# 3_Communication.net
KiCad netlist of a schematic drawn in Altium Designer
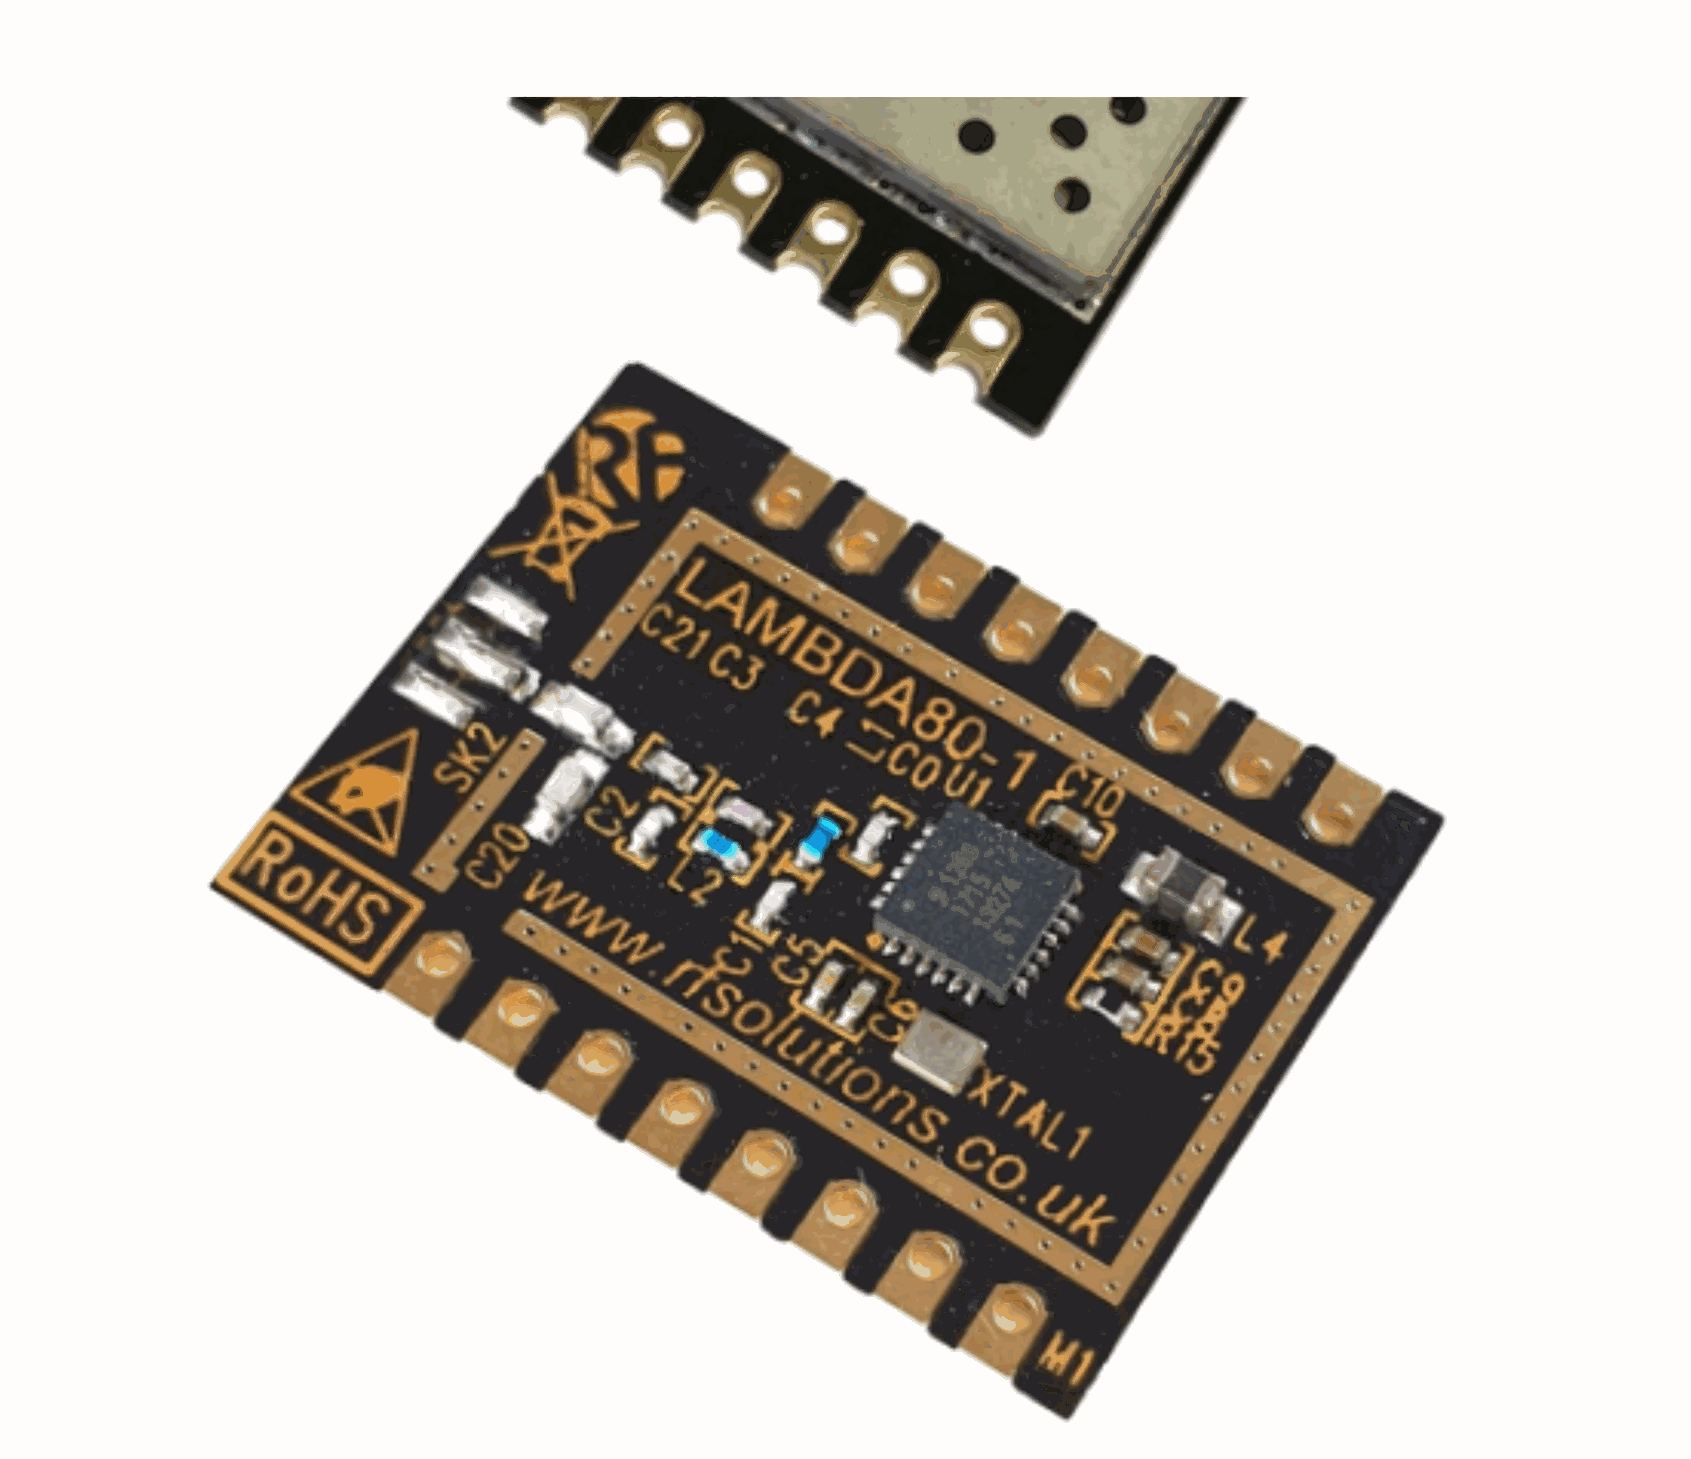
[diagram p0: 3_Communication.SchDoc, top middle]
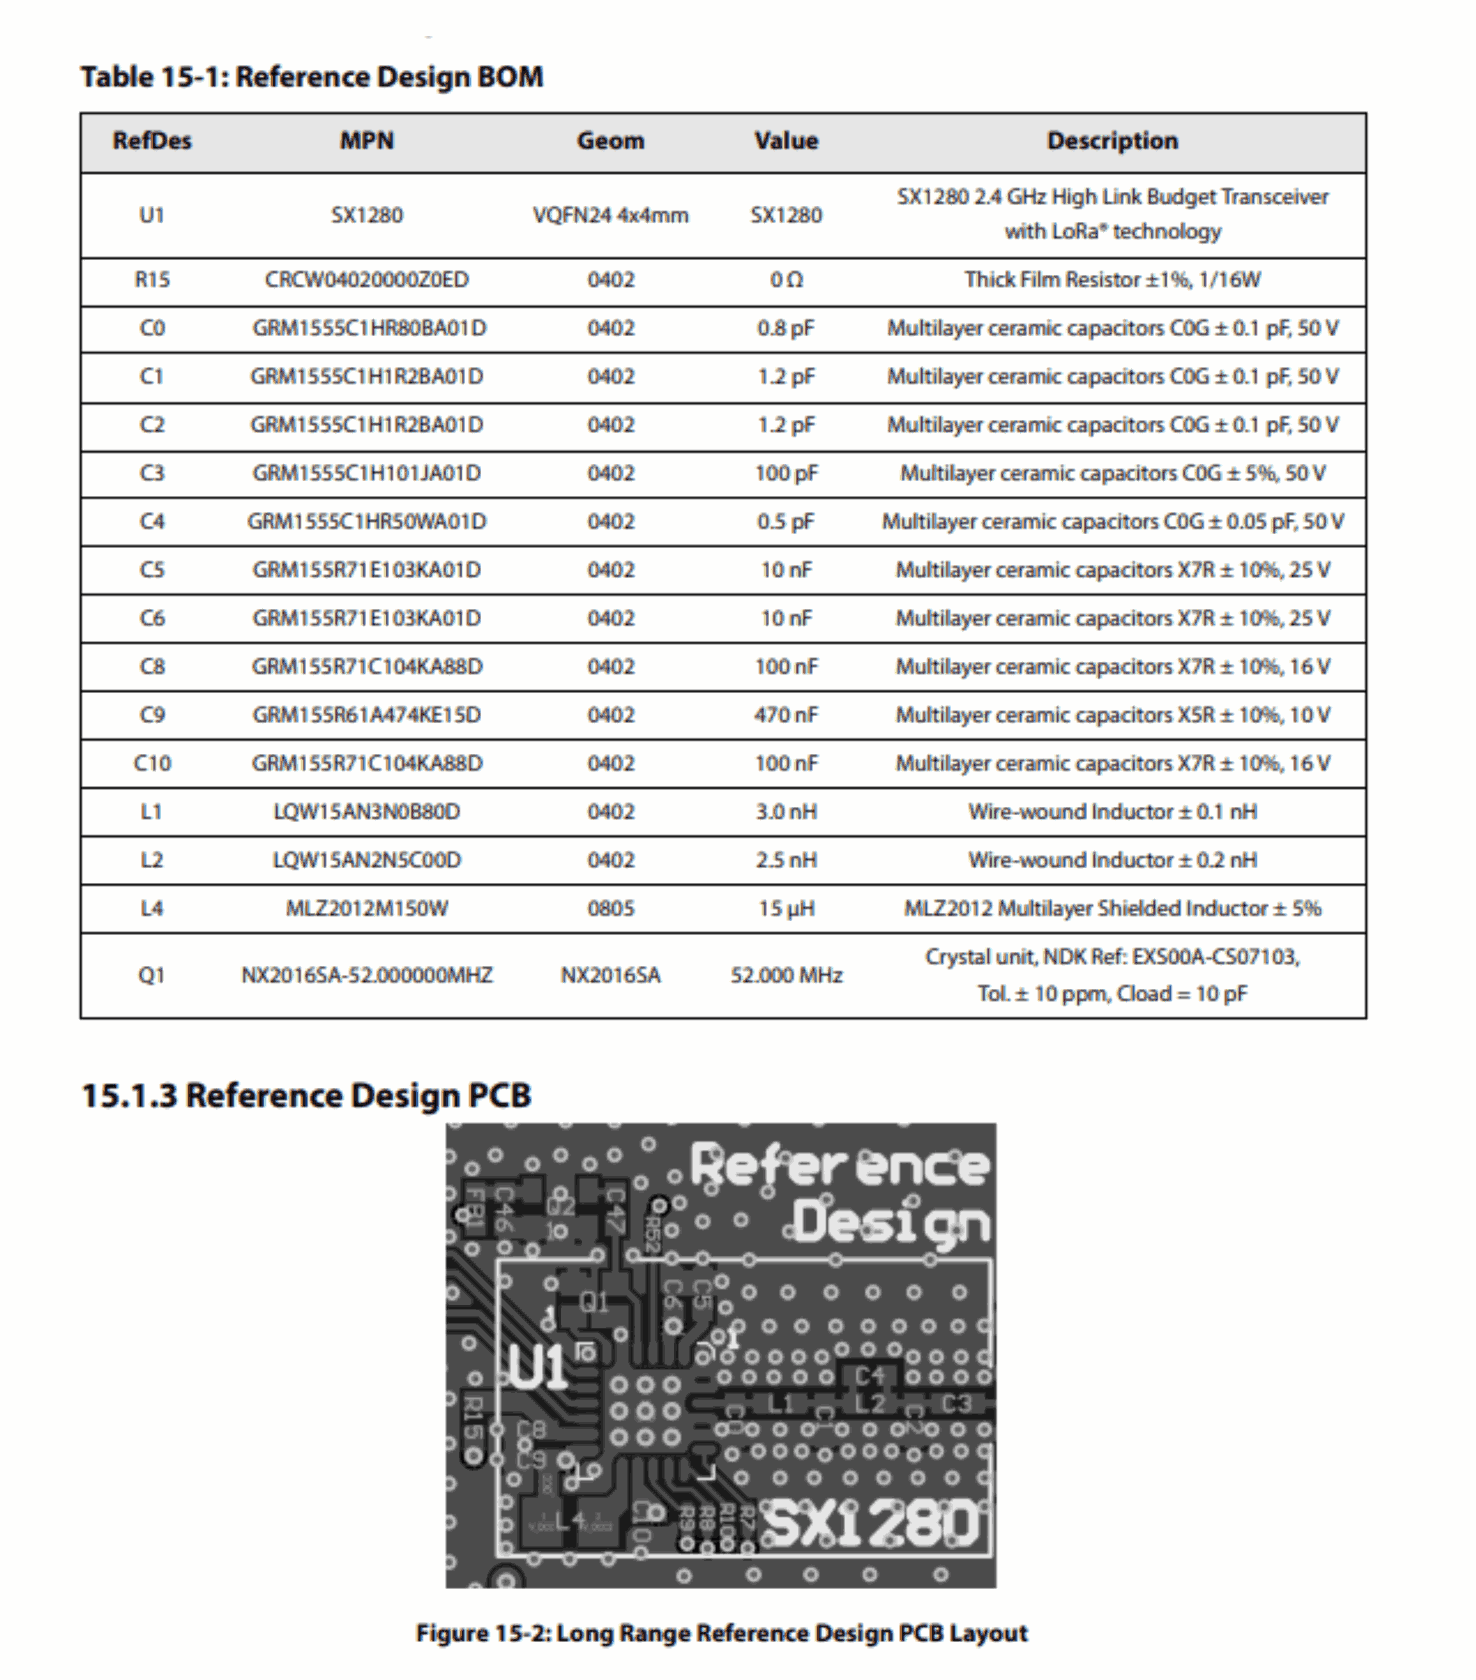
[diagram p1: 3_Communication.SchDoc, top right]
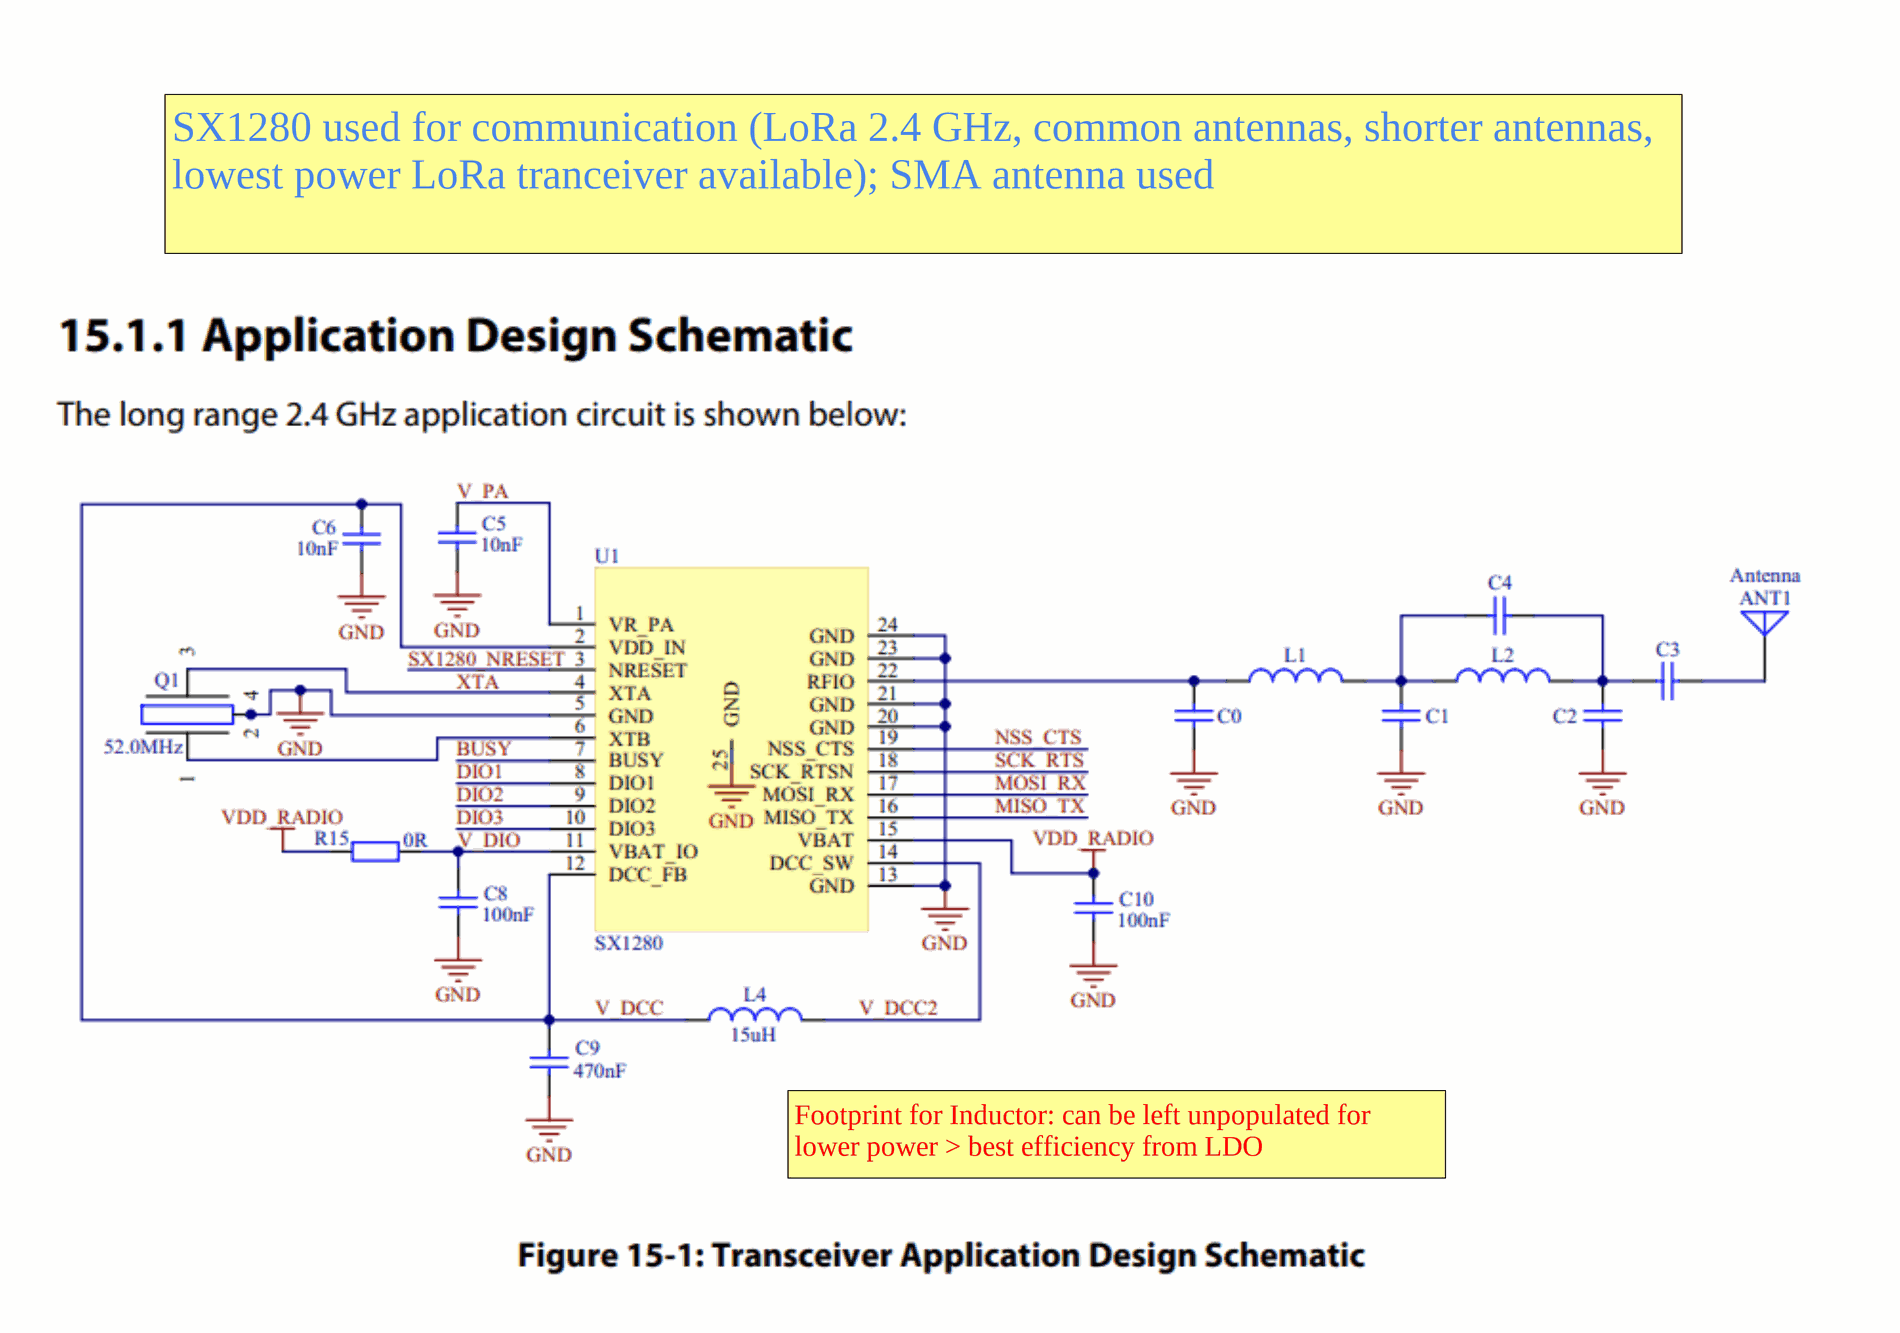
[diagram p2: 3_Communication.SchDoc, bottom left]
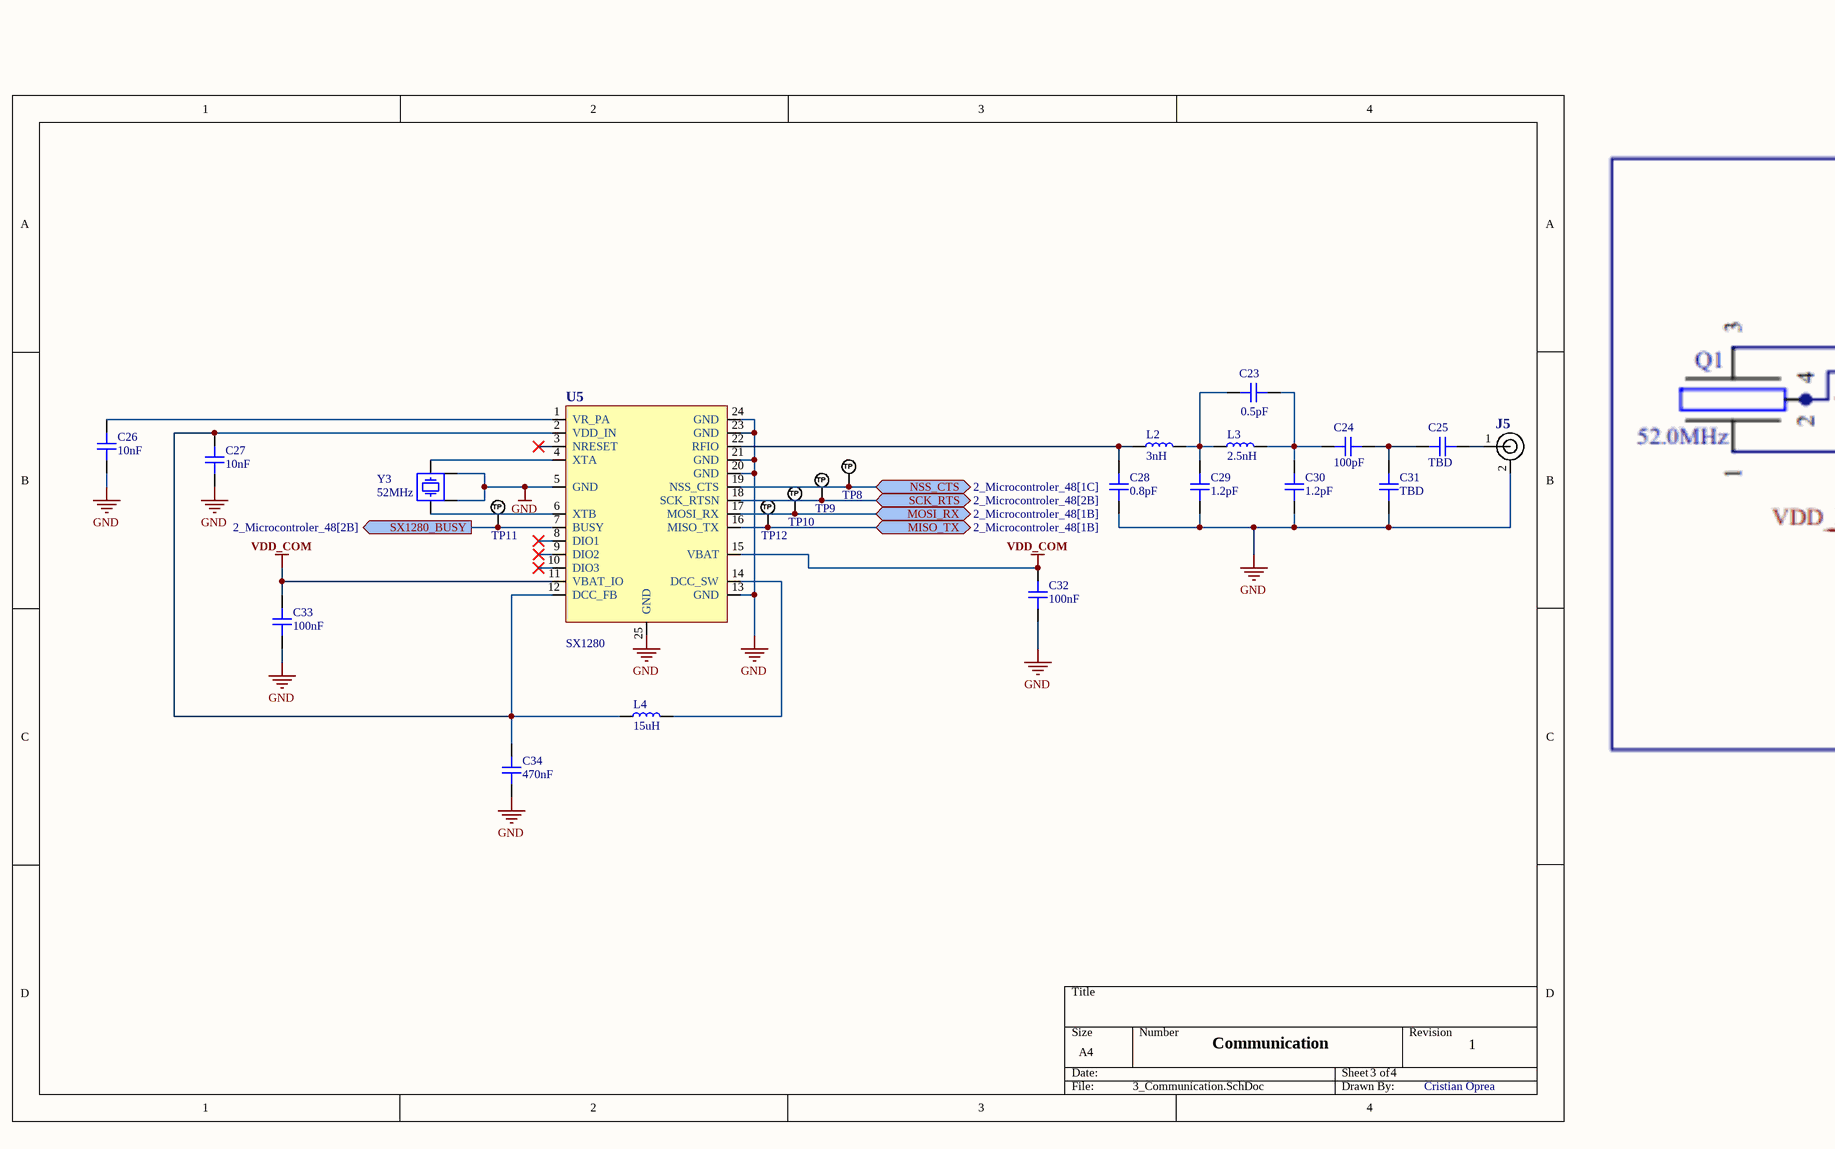
[diagram p3: 3_Communication.SchDoc, bottom middle]
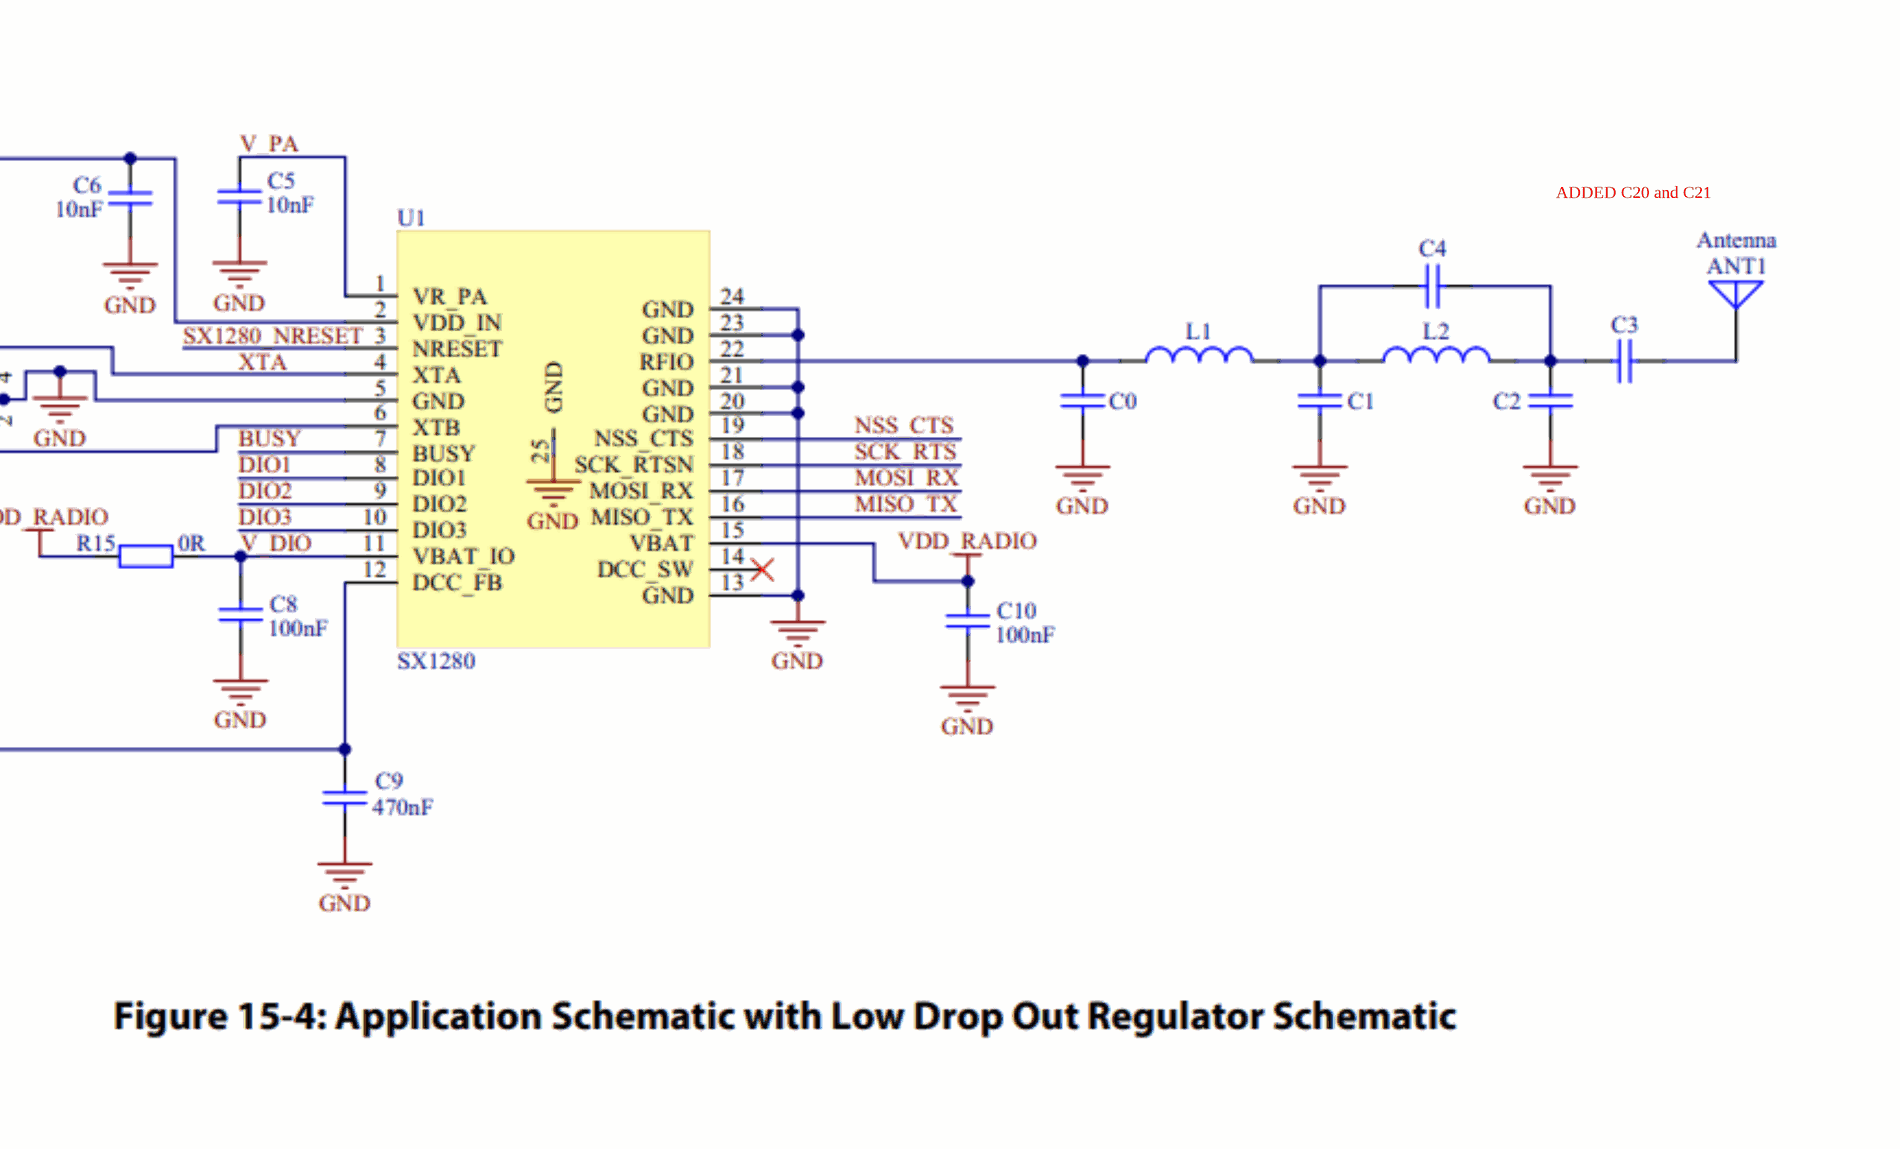
[diagram p4: 3_Communication.SchDoc, bottom right]

(export (version "E")
  (design (tool "Eeschema 10.0.6"))
  (components
    (comp (ref "C23")
      (value "0.5pF")
      (footprint "C0603")
      (description "Capacitor SMD 0603")
      (libsource (lib "Schlib_H2") (part "CAP_0603"))
    )
    (comp (ref "C24")
      (value "100pF")
      (footprint "C0603")
      (description "Capacitor SMD 0603")
      (libsource (lib "Schlib_H2") (part "CAP_0603"))
    )
    (comp (ref "C25")
      (value "TBD")
      (footprint "C0805")
      (description "Capacitor SMD 0805")
      (libsource (lib "Schlib_H2") (part "CAP_0603"))
    )
    (comp (ref "C26")
      (value "10nF")
      (footprint "C0603")
      (description "Capacitor SMD 0603")
      (libsource (lib "Schlib_H2") (part "CAP_0603"))
    )
    (comp (ref "C27")
      (value "10nF")
      (footprint "C0603")
      (description "Capacitor SMD 0603")
      (libsource (lib "Schlib_H2") (part "CAP_0603"))
    )
    (comp (ref "C28")
      (value "0.8pF")
      (footprint "C0603")
      (description "Capacitor SMD 0805")
      (libsource (lib "Schlib_H2") (part "CAP_0805"))
    )
    (comp (ref "C29")
      (value "1.2pF")
      (footprint "C0603")
      (description "Capacitor SMD 0603")
      (libsource (lib "Schlib_H2") (part "CAP_0603"))
    )
    (comp (ref "C30")
      (value "1.2pF")
      (footprint "C0603")
      (description "Capacitor SMD 0603")
      (libsource (lib "Schlib_H2") (part "CAP_0603"))
    )
    (comp (ref "C31")
      (value "TBD")
      (footprint "C0805")
      (description "Capacitor SMD 0805")
      (libsource (lib "Schlib_H2") (part "CAP_0603"))
    )
    (comp (ref "C32")
      (value "100nF")
      (footprint "C0603")
      (description "Capacitor SMD 0603")
      (libsource (lib "Schlib_H2") (part "CAP_0603"))
    )
    (comp (ref "C33")
      (value "100nF")
      (footprint "C0603")
      (description "Capacitor SMD 0603")
      (libsource (lib "Schlib_H2") (part "CAP_0603"))
    )
    (comp (ref "C34")
      (value "470nF")
      (footprint "C0603")
      (description "Capacitor SMD 0603")
      (libsource (lib "Schlib_H2") (part "CAP_0603"))
    )
    (comp (ref "J5")
      (value "SMA_EDGE_CONN")
      (footprint "CON_SMA-EDGE-S")
      (description "RF Connector SMA Female 50 Ohms 18 GHz PCB Edge Mount")
      (fields
        (field (name "MANUFACTURER") "RF Solutions")
        (field (name "MANUFACTURER PART NUMBER") "CON-SMA-EDGE-S")
      )
      (libsource (lib "Schlib_H2") (part "CON-SMA-EDGE-S"))
    )
    (comp (ref "L2")
      (value "3nH")
      (footprint "R0603")
      (description "Inductor SMD 0603")
      (libsource (lib "Schlib_H2") (part "IND_0603"))
    )
    (comp (ref "L3")
      (value "2.5nH")
      (footprint "R0603")
      (description "Inductor SMD 0603")
      (libsource (lib "Schlib_H2") (part "IND_0603"))
    )
    (comp (ref "L4")
      (value "15uH")
      (footprint "IND_3.2_4")
      (description "Inductor SMD 0603")
      (libsource (lib "Schlib_H2") (part "IND_0603"))
    )
    (comp (ref "TP8")
      (value "TP_NOBOM")
      (footprint "TEST_PAD_THD")
      (description "Test Point Round 1mm (NO BOM)")
      (libsource (lib "Schlib_H2") (part "TEST_POINT_RND_1MM"))
    )
    (comp (ref "TP9")
      (value "TP_NOBOM")
      (footprint "TEST_PAD_THD")
      (description "Test Point Round 1mm (NO BOM)")
      (libsource (lib "Schlib_H2") (part "TEST_POINT_RND_1MM"))
    )
    (comp (ref "TP10")
      (value "TP_NOBOM")
      (footprint "TEST_PAD_THD")
      (description "Test Point Round 1mm (NO BOM)")
      (libsource (lib "Schlib_H2") (part "TEST_POINT_RND_1MM"))
    )
    (comp (ref "TP11")
      (value "TP_NOBOM")
      (footprint "TEST_PAD_THD")
      (description "Test Point Round 1mm (NO BOM)")
      (libsource (lib "Schlib_H2") (part "TEST_POINT_RND_1MM"))
    )
    (comp (ref "TP12")
      (value "TP_NOBOM")
      (footprint "TEST_PAD_THD")
      (description "Test Point Round 1mm (NO BOM)")
      (libsource (lib "Schlib_H2") (part "TEST_POINT_RND_1MM"))
    )
    (comp (ref "U5")
      (value "SX1280")
      (footprint "QFN-24_4x4_0.5")
      (description "Low power LoRa transceiver operating at 2.4GHz with ranging capability")
      (libsource (lib "Schlib_H2") (part "SX1280"))
    )
    (comp (ref "Y3")
      (value "52MHz")
      (footprint "CRYSTAL_2016_4P")
      (description "Crystal")
      (fields
        (field (name "MANUFACTURER") "Epson")
        (field (name "MANUFACTURER PART NUMBER") "TSX-3225 24.0000MF15X-AC")
      )
      (libsource (lib "Schlib_H2") (part "Crystal"))
    )
  )
  (nets
    (net (code "1") (name "/MISO_TX") (class "Default")
      (node (ref "TP12") (pin "1") (pinfunction "TP_1") (pintype "passive"))
      (node (ref "U5") (pin "16") (pinfunction "MISO_TX_16") (pintype "passive"))
    )
    (net (code "2") (name "/MOSI_RX") (class "Default")
      (node (ref "TP10") (pin "1") (pinfunction "TP_1") (pintype "passive"))
      (node (ref "U5") (pin "17") (pinfunction "MOSI_RX_17") (pintype "passive"))
    )
    (net (code "3") (name "/NSS_CTS") (class "Default")
      (node (ref "TP8") (pin "1") (pinfunction "TP_1") (pintype "passive"))
      (node (ref "U5") (pin "19") (pinfunction "NSS_CTS_19") (pintype "passive"))
    )
    (net (code "4") (name "/SCK_RTS") (class "Default")
      (node (ref "TP9") (pin "1") (pinfunction "TP_1") (pintype "passive"))
      (node (ref "U5") (pin "18") (pinfunction "SCK_RTSN_18") (pintype "passive"))
    )
    (net (code "5") (name "/SX1280_BUSY") (class "Default")
      (node (ref "TP11") (pin "1") (pinfunction "TP_1") (pintype "passive"))
      (node (ref "U5") (pin "7") (pinfunction "BUSY_7") (pintype "passive"))
    )
    (net (code "6") (name "GND") (class "Default")
      (node (ref "C26") (pin "1") (pinfunction "1_1") (pintype "passive"))
      (node (ref "C27") (pin "1") (pinfunction "1_1") (pintype "passive"))
      (node (ref "C28") (pin "1") (pinfunction "1_1") (pintype "passive"))
      (node (ref "C29") (pin "1") (pinfunction "1_1") (pintype "passive"))
      (node (ref "C30") (pin "1") (pinfunction "1_1") (pintype "passive"))
      (node (ref "C31") (pin "1") (pinfunction "1_1") (pintype "passive"))
      (node (ref "C32") (pin "1") (pinfunction "1_1") (pintype "passive"))
      (node (ref "C33") (pin "1") (pinfunction "1_1") (pintype "passive"))
      (node (ref "C34") (pin "1") (pinfunction "1_1") (pintype "passive"))
      (node (ref "J5") (pin "2") (pinfunction "2_2") (pintype "passive"))
      (node (ref "U5") (pin "13") (pinfunction "GND_13") (pintype "passive"))
      (node (ref "U5") (pin "20") (pinfunction "GND_20") (pintype "passive"))
      (node (ref "U5") (pin "21") (pinfunction "GND_21") (pintype "passive"))
      (node (ref "U5") (pin "23") (pinfunction "GND_23") (pintype "passive"))
      (node (ref "U5") (pin "24") (pinfunction "GND_24") (pintype "passive"))
      (node (ref "U5") (pin "25") (pinfunction "GND_25") (pintype "passive"))
      (node (ref "U5") (pin "5") (pinfunction "GND_5") (pintype "passive"))
      (node (ref "Y3") (pin "2") (pinfunction "2_2") (pintype "passive"))
      (node (ref "Y3") (pin "4") (pinfunction "4_4") (pintype "passive"))
    )
    (net (code "7") (name "Net-(C23-Pad1)") (class "Default")
      (node (ref "C23") (pin "1") (pinfunction "1_1") (pintype "passive"))
      (node (ref "C24") (pin "2") (pinfunction "2_2") (pintype "passive"))
      (node (ref "C30") (pin "2") (pinfunction "2_2") (pintype "passive"))
      (node (ref "L3") (pin "2") (pinfunction "2_2") (pintype "passive"))
    )
    (net (code "8") (name "Net-(C23-Pad2)") (class "Default")
      (node (ref "C23") (pin "2") (pinfunction "2_2") (pintype "passive"))
      (node (ref "C29") (pin "2") (pinfunction "2_2") (pintype "passive"))
      (node (ref "L2") (pin "2") (pinfunction "2_2") (pintype "passive"))
      (node (ref "L3") (pin "1") (pinfunction "1_1") (pintype "passive"))
    )
    (net (code "9") (name "Net-(C24-Pad1)") (class "Default")
      (node (ref "C24") (pin "1") (pinfunction "1_1") (pintype "passive"))
      (node (ref "C25") (pin "2") (pinfunction "2_2") (pintype "passive"))
      (node (ref "C31") (pin "2") (pinfunction "2_2") (pintype "passive"))
    )
    (net (code "10") (name "Net-(C25-Pad1)") (class "Default")
      (node (ref "C25") (pin "1") (pinfunction "1_1") (pintype "passive"))
      (node (ref "J5") (pin "1") (pinfunction "1_1") (pintype "passive"))
    )
    (net (code "11") (name "Net-(U5-DCC_FB)") (class "Default")
      (node (ref "C27") (pin "2") (pinfunction "2_2") (pintype "passive"))
      (node (ref "C34") (pin "2") (pinfunction "2_2") (pintype "passive"))
      (node (ref "L4") (pin "1") (pinfunction "1_1") (pintype "passive"))
      (node (ref "U5") (pin "12") (pinfunction "DCC_FB_12") (pintype "passive"))
      (node (ref "U5") (pin "2") (pinfunction "VDD_IN_2") (pintype "passive"))
    )
    (net (code "12") (name "Net-(U5-DCC_SW)") (class "Default")
      (node (ref "L4") (pin "2") (pinfunction "2_2") (pintype "passive"))
      (node (ref "U5") (pin "14") (pinfunction "DCC_SW_14") (pintype "passive"))
    )
    (net (code "13") (name "Net-(U5-RFIO)") (class "Default")
      (node (ref "C28") (pin "2") (pinfunction "2_2") (pintype "passive"))
      (node (ref "L2") (pin "1") (pinfunction "1_1") (pintype "passive"))
      (node (ref "U5") (pin "22") (pinfunction "RFIO_22") (pintype "passive"))
    )
    (net (code "14") (name "Net-(U5-VR_PA)") (class "Default")
      (node (ref "C26") (pin "2") (pinfunction "2_2") (pintype "passive"))
      (node (ref "U5") (pin "1") (pinfunction "VR_PA_1") (pintype "passive"))
    )
    (net (code "15") (name "Net-(U5-XTA)") (class "Default")
      (node (ref "U5") (pin "4") (pinfunction "XTA_4") (pintype "passive"))
      (node (ref "Y3") (pin "3") (pinfunction "3_3") (pintype "passive"))
    )
    (net (code "16") (name "Net-(U5-XTB)") (class "Default")
      (node (ref "U5") (pin "6") (pinfunction "XTB_6") (pintype "passive"))
      (node (ref "Y3") (pin "1") (pinfunction "1_1") (pintype "passive"))
    )
    (net (code "17") (name "VDD_COM") (class "Default")
      (node (ref "C32") (pin "2") (pinfunction "2_2") (pintype "passive"))
      (node (ref "C33") (pin "2") (pinfunction "2_2") (pintype "passive"))
      (node (ref "U5") (pin "11") (pinfunction "VBAT_IO_11") (pintype "passive"))
      (node (ref "U5") (pin "15") (pinfunction "VBAT_15") (pintype "passive"))
    )
    (net (code "18") (name "unconnected-(U5-DIO1-Pad8)") (class "Default")
      (node (ref "U5") (pin "8") (pinfunction "DIO1_8") (pintype "passive+no_connect"))
    )
    (net (code "19") (name "unconnected-(U5-DIO2-Pad9)") (class "Default")
      (node (ref "U5") (pin "9") (pinfunction "DIO2_9") (pintype "passive+no_connect"))
    )
    (net (code "20") (name "unconnected-(U5-DIO3-Pad10)") (class "Default")
      (node (ref "U5") (pin "10") (pinfunction "DIO3_10") (pintype "passive+no_connect"))
    )
    (net (code "21") (name "unconnected-(U5-NRESET-Pad3)") (class "Default")
      (node (ref "U5") (pin "3") (pinfunction "NRESET_3") (pintype "passive+no_connect"))
    )
  )
)
